# MOTOR.net
KiCad netlist of a schematic drawn in EAGLE
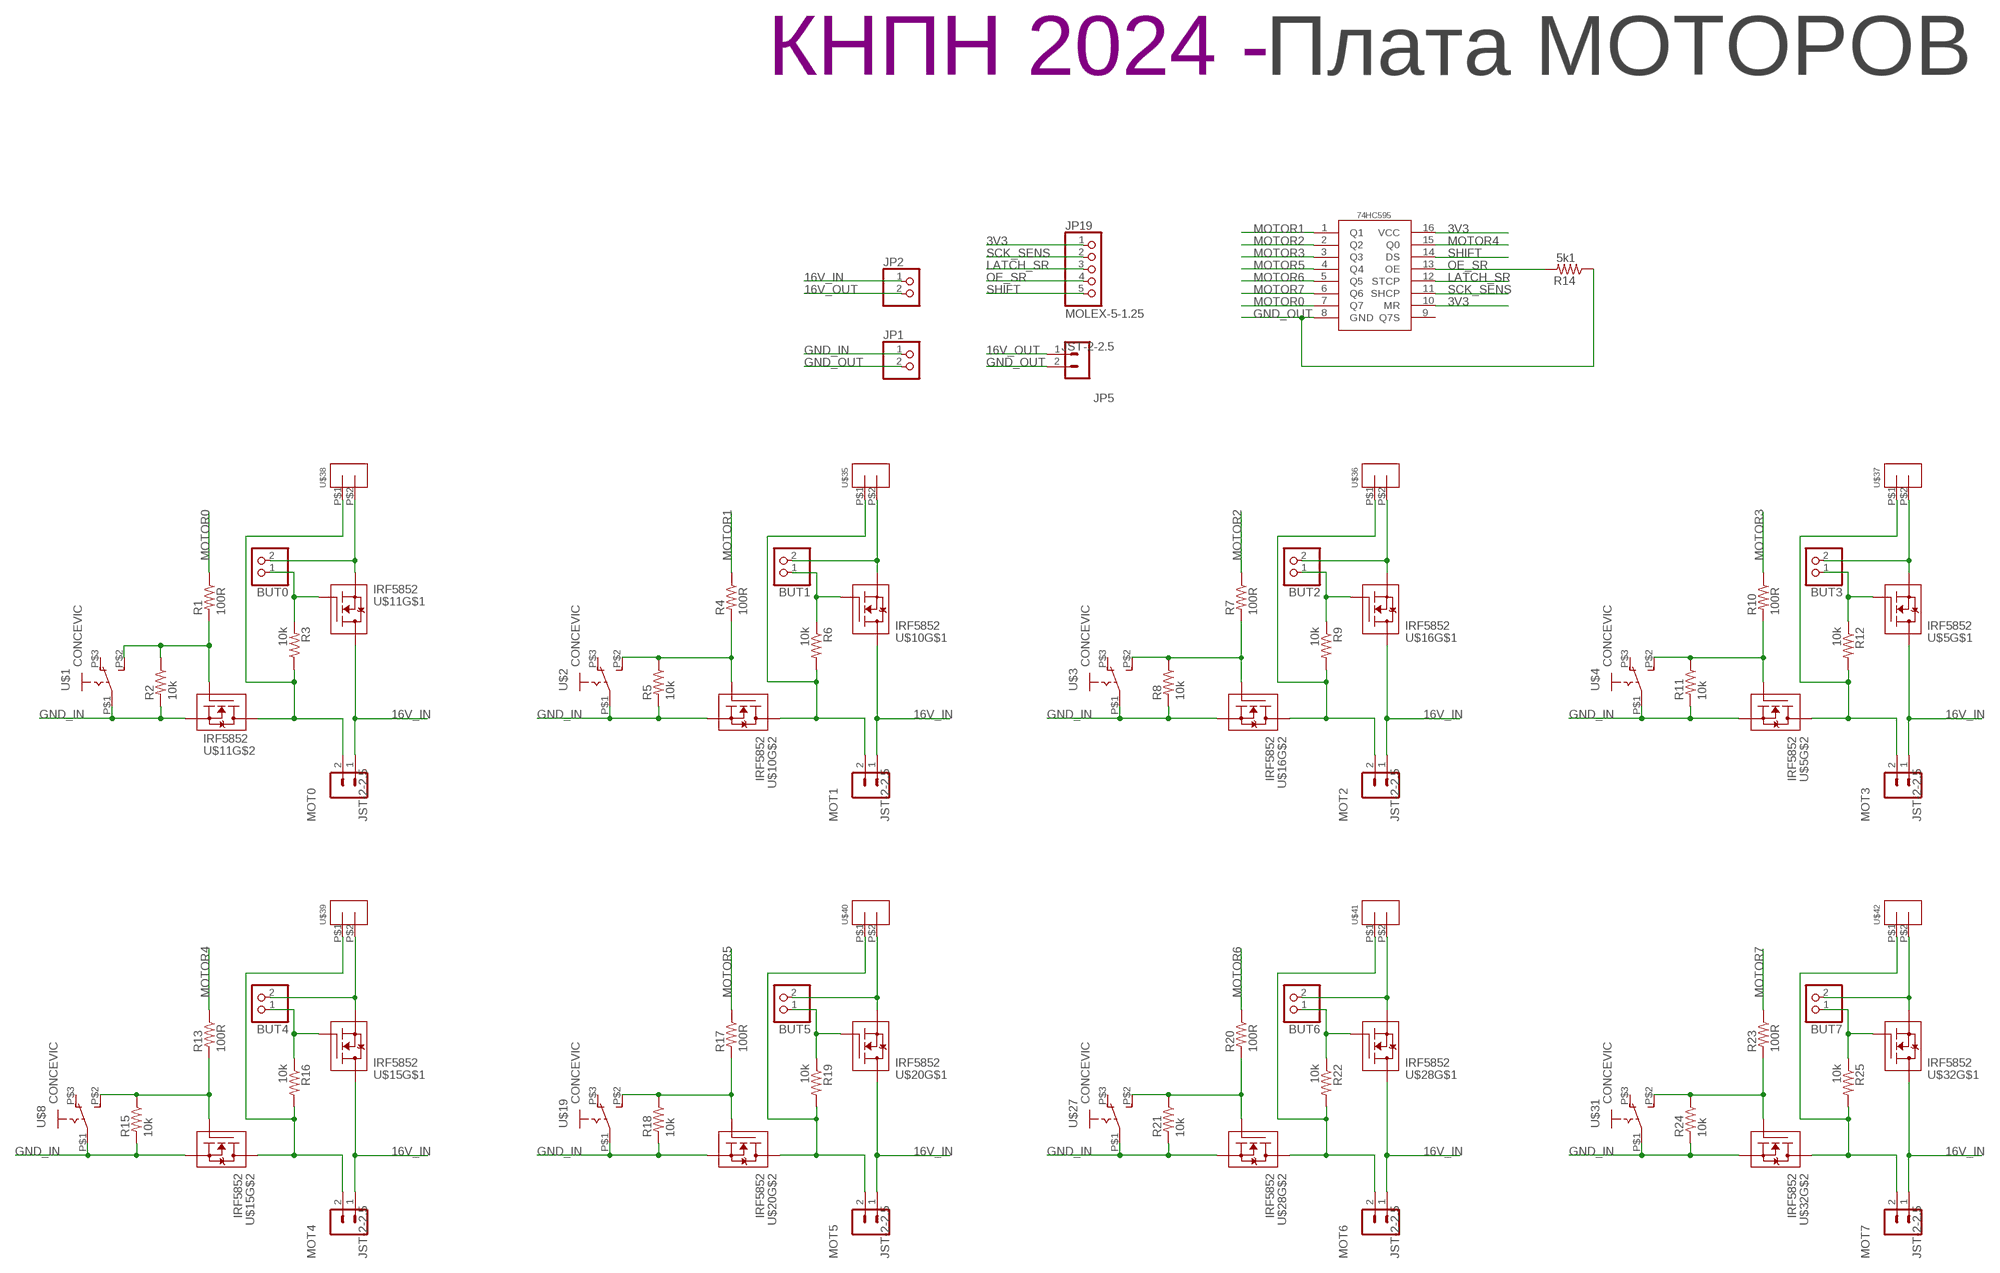
[diagram p0: schematic, sheet 1]

(export (version "E")
  (design (tool "Eeschema 10.0.6"))
  (components
    (comp (ref "BUT0")
      (value "PINHD-1X2")
      (footprint "eagle-import:1X02")
      (libsource (lib "eagle-import") (part "PINHD-1X2"))
    )
    (comp (ref "BUT1")
      (value "PINHD-1X2")
      (footprint "eagle-import:1X02")
      (libsource (lib "eagle-import") (part "PINHD-1X2"))
    )
    (comp (ref "BUT2")
      (value "PINHD-1X2")
      (footprint "eagle-import:1X02")
      (libsource (lib "eagle-import") (part "PINHD-1X2"))
    )
    (comp (ref "BUT3")
      (value "PINHD-1X2")
      (footprint "eagle-import:1X02")
      (libsource (lib "eagle-import") (part "PINHD-1X2"))
    )
    (comp (ref "BUT4")
      (value "PINHD-1X2")
      (footprint "eagle-import:1X02")
      (libsource (lib "eagle-import") (part "PINHD-1X2"))
    )
    (comp (ref "BUT5")
      (value "PINHD-1X2")
      (footprint "eagle-import:1X02")
      (libsource (lib "eagle-import") (part "PINHD-1X2"))
    )
    (comp (ref "BUT6")
      (value "PINHD-1X2")
      (footprint "eagle-import:1X02")
      (libsource (lib "eagle-import") (part "PINHD-1X2"))
    )
    (comp (ref "BUT7")
      (value "PINHD-1X2")
      (footprint "eagle-import:1X02")
      (libsource (lib "eagle-import") (part "PINHD-1X2"))
    )
    (comp (ref "JP1")
      (value "PINHD-1X2/90")
      (footprint "eagle-import:1X02_90")
      (libsource (lib "eagle-import") (part "PINHD-1X2/90"))
    )
    (comp (ref "JP2")
      (value "PINHD-1X2/90")
      (footprint "eagle-import:1X02_90")
      (libsource (lib "eagle-import") (part "PINHD-1X2/90"))
    )
    (comp (ref "JP5")
      (value "JST-2-2.5")
      (footprint "eagle-import:JST-2-2.5")
      (libsource (lib "eagle-import") (part "JST-2-2.5"))
    )
    (comp (ref "JP19")
      (value "MOLEX-5-1.25")
      (footprint "eagle-import:53047-05")
      (libsource (lib "eagle-import") (part "MOLEX-5-1.25"))
    )
    (comp (ref "MOT0")
      (value "JST-2-2.5")
      (footprint "eagle-import:JST-2-2.5")
      (libsource (lib "eagle-import") (part "JST-2-2.5"))
    )
    (comp (ref "MOT1")
      (value "JST-2-2.5")
      (footprint "eagle-import:JST-2-2.5")
      (libsource (lib "eagle-import") (part "JST-2-2.5"))
    )
    (comp (ref "MOT2")
      (value "JST-2-2.5")
      (footprint "eagle-import:JST-2-2.5")
      (libsource (lib "eagle-import") (part "JST-2-2.5"))
    )
    (comp (ref "MOT3")
      (value "JST-2-2.5")
      (footprint "eagle-import:JST-2-2.5")
      (libsource (lib "eagle-import") (part "JST-2-2.5"))
    )
    (comp (ref "MOT4")
      (value "JST-2-2.5")
      (footprint "eagle-import:JST-2-2.5")
      (libsource (lib "eagle-import") (part "JST-2-2.5"))
    )
    (comp (ref "MOT5")
      (value "JST-2-2.5")
      (footprint "eagle-import:JST-2-2.5")
      (libsource (lib "eagle-import") (part "JST-2-2.5"))
    )
    (comp (ref "MOT6")
      (value "JST-2-2.5")
      (footprint "eagle-import:JST-2-2.5")
      (libsource (lib "eagle-import") (part "JST-2-2.5"))
    )
    (comp (ref "MOT7")
      (value "JST-2-2.5")
      (footprint "eagle-import:JST-2-2.5")
      (libsource (lib "eagle-import") (part "JST-2-2.5"))
    )
    (comp (ref "R1")
      (value "100R")
      (footprint "eagle-import:R0603")
      (libsource (lib "eagle-import") (part "R-US_R0603"))
    )
    (comp (ref "R2")
      (value "10k")
      (footprint "eagle-import:R0603")
      (libsource (lib "eagle-import") (part "R-US_R0603"))
    )
    (comp (ref "R3")
      (value "10k")
      (footprint "eagle-import:R0603")
      (libsource (lib "eagle-import") (part "R-US_R0603"))
    )
    (comp (ref "R4")
      (value "100R")
      (footprint "eagle-import:R0603")
      (libsource (lib "eagle-import") (part "R-US_R0603"))
    )
    (comp (ref "R5")
      (value "10k")
      (footprint "eagle-import:R0603")
      (libsource (lib "eagle-import") (part "R-US_R0603"))
    )
    (comp (ref "R6")
      (value "10k")
      (footprint "eagle-import:R0603")
      (libsource (lib "eagle-import") (part "R-US_R0603"))
    )
    (comp (ref "R7")
      (value "100R")
      (footprint "eagle-import:R0603")
      (libsource (lib "eagle-import") (part "R-US_R0603"))
    )
    (comp (ref "R8")
      (value "10k")
      (footprint "eagle-import:R0603")
      (libsource (lib "eagle-import") (part "R-US_R0603"))
    )
    (comp (ref "R9")
      (value "10k")
      (footprint "eagle-import:R0603")
      (libsource (lib "eagle-import") (part "R-US_R0603"))
    )
    (comp (ref "R10")
      (value "100R")
      (footprint "eagle-import:R0603")
      (libsource (lib "eagle-import") (part "R-US_R0603"))
    )
    (comp (ref "R11")
      (value "10k")
      (footprint "eagle-import:R0603")
      (libsource (lib "eagle-import") (part "R-US_R0603"))
    )
    (comp (ref "R12")
      (value "10k")
      (footprint "eagle-import:R0603")
      (libsource (lib "eagle-import") (part "R-US_R0603"))
    )
    (comp (ref "R13")
      (value "100R")
      (footprint "eagle-import:R0603")
      (libsource (lib "eagle-import") (part "R-US_R0603"))
    )
    (comp (ref "R14")
      (value "5k1")
      (footprint "eagle-import:R0603")
      (libsource (lib "eagle-import") (part "R-US_R0603"))
    )
    (comp (ref "R15")
      (value "10k")
      (footprint "eagle-import:R0603")
      (libsource (lib "eagle-import") (part "R-US_R0603"))
    )
    (comp (ref "R16")
      (value "10k")
      (footprint "eagle-import:R0603")
      (libsource (lib "eagle-import") (part "R-US_R0603"))
    )
    (comp (ref "R17")
      (value "100R")
      (footprint "eagle-import:R0603")
      (libsource (lib "eagle-import") (part "R-US_R0603"))
    )
    (comp (ref "R18")
      (value "10k")
      (footprint "eagle-import:R0603")
      (libsource (lib "eagle-import") (part "R-US_R0603"))
    )
    (comp (ref "R19")
      (value "10k")
      (footprint "eagle-import:R0603")
      (libsource (lib "eagle-import") (part "R-US_R0603"))
    )
    (comp (ref "R20")
      (value "100R")
      (footprint "eagle-import:R0603")
      (libsource (lib "eagle-import") (part "R-US_R0603"))
    )
    (comp (ref "R21")
      (value "10k")
      (footprint "eagle-import:R0603")
      (libsource (lib "eagle-import") (part "R-US_R0603"))
    )
    (comp (ref "R22")
      (value "10k")
      (footprint "eagle-import:R0603")
      (libsource (lib "eagle-import") (part "R-US_R0603"))
    )
    (comp (ref "R23")
      (value "100R")
      (footprint "eagle-import:R0603")
      (libsource (lib "eagle-import") (part "R-US_R0603"))
    )
    (comp (ref "R24")
      (value "10k")
      (footprint "eagle-import:R0603")
      (libsource (lib "eagle-import") (part "R-US_R0603"))
    )
    (comp (ref "R25")
      (value "10k")
      (footprint "eagle-import:R0603")
      (libsource (lib "eagle-import") (part "R-US_R0603"))
    )
    (comp (ref "U$1")
      (value "CONCEVIC")
      (footprint "eagle-import:CONCEVIC")
      (libsource (lib "eagle-import") (part "CONCEVIC"))
    )
    (comp (ref "U$2")
      (value "CONCEVIC")
      (footprint "eagle-import:CONCEVIC")
      (libsource (lib "eagle-import") (part "CONCEVIC"))
    )
    (comp (ref "U$3")
      (value "CONCEVIC")
      (footprint "eagle-import:CONCEVIC")
      (libsource (lib "eagle-import") (part "CONCEVIC"))
    )
    (comp (ref "U$4")
      (value "CONCEVIC")
      (footprint "eagle-import:CONCEVIC")
      (libsource (lib "eagle-import") (part "CONCEVIC"))
    )
    (comp (ref "U$5")
      (value "IRF5852")
      (footprint "eagle-import:TSOP-6")
      (libsource (lib "eagle-import") (part "IRF5852"))
    )
    (comp (ref "U$8")
      (value "CONCEVIC")
      (footprint "eagle-import:CONCEVIC")
      (libsource (lib "eagle-import") (part "CONCEVIC"))
    )
    (comp (ref "U$9")
      (value "Плата МОТОРОВ")
      (footprint "eagle-import:LOGO")
      (libsource (lib "eagle-import") (part "LOGOPCB-{dblquote}{dblquote}"))
    )
    (comp (ref "U$10")
      (value "IRF5852")
      (footprint "eagle-import:TSOP-6")
      (libsource (lib "eagle-import") (part "IRF5852"))
    )
    (comp (ref "U$11")
      (value "IRF5852")
      (footprint "eagle-import:TSOP-6")
      (libsource (lib "eagle-import") (part "IRF5852"))
    )
    (comp (ref "U$13")
      (value "74HC595")
      (footprint "eagle-import:TSSOP16")
      (libsource (lib "eagle-import") (part "74HC595"))
    )
    (comp (ref "U$15")
      (value "IRF5852")
      (footprint "eagle-import:TSOP-6")
      (libsource (lib "eagle-import") (part "IRF5852"))
    )
    (comp (ref "U$16")
      (value "IRF5852")
      (footprint "eagle-import:TSOP-6")
      (libsource (lib "eagle-import") (part "IRF5852"))
    )
    (comp (ref "U$19")
      (value "CONCEVIC")
      (footprint "eagle-import:CONCEVIC")
      (libsource (lib "eagle-import") (part "CONCEVIC"))
    )
    (comp (ref "U$20")
      (value "IRF5852")
      (footprint "eagle-import:TSOP-6")
      (libsource (lib "eagle-import") (part "IRF5852"))
    )
    (comp (ref "U$27")
      (value "CONCEVIC")
      (footprint "eagle-import:CONCEVIC")
      (libsource (lib "eagle-import") (part "CONCEVIC"))
    )
    (comp (ref "U$28")
      (value "IRF5852")
      (footprint "eagle-import:TSOP-6")
      (libsource (lib "eagle-import") (part "IRF5852"))
    )
    (comp (ref "U$31")
      (value "CONCEVIC")
      (footprint "eagle-import:CONCEVIC")
      (libsource (lib "eagle-import") (part "CONCEVIC"))
    )
    (comp (ref "U$32")
      (value "IRF5852")
      (footprint "eagle-import:TSOP-6")
      (libsource (lib "eagle-import") (part "IRF5852"))
    )
    (comp (ref "U$35")
      (value "CONTACT_SIDE_4MM_2PIN")
      (footprint "eagle-import:CONTACT_SIDE_4MM_2PIN")
      (libsource (lib "eagle-import") (part "CONTACT_SIDE_4MM_2PIN"))
    )
    (comp (ref "U$36")
      (value "CONTACT_SIDE_4MM_2PIN")
      (footprint "eagle-import:CONTACT_SIDE_4MM_2PIN")
      (libsource (lib "eagle-import") (part "CONTACT_SIDE_4MM_2PIN"))
    )
    (comp (ref "U$37")
      (value "CONTACT_SIDE_4MM_2PIN")
      (footprint "eagle-import:CONTACT_SIDE_4MM_2PIN")
      (libsource (lib "eagle-import") (part "CONTACT_SIDE_4MM_2PIN"))
    )
    (comp (ref "U$38")
      (value "CONTACT_SIDE_4MM_2PIN")
      (footprint "eagle-import:CONTACT_SIDE_4MM_2PIN")
      (libsource (lib "eagle-import") (part "CONTACT_SIDE_4MM_2PIN"))
    )
    (comp (ref "U$39")
      (value "CONTACT_SIDE_4MM_2PIN")
      (footprint "eagle-import:CONTACT_SIDE_4MM_2PIN")
      (libsource (lib "eagle-import") (part "CONTACT_SIDE_4MM_2PIN"))
    )
    (comp (ref "U$40")
      (value "CONTACT_SIDE_4MM_2PIN")
      (footprint "eagle-import:CONTACT_SIDE_4MM_2PIN")
      (libsource (lib "eagle-import") (part "CONTACT_SIDE_4MM_2PIN"))
    )
    (comp (ref "U$41")
      (value "CONTACT_SIDE_4MM_2PIN")
      (footprint "eagle-import:CONTACT_SIDE_4MM_2PIN")
      (libsource (lib "eagle-import") (part "CONTACT_SIDE_4MM_2PIN"))
    )
    (comp (ref "U$42")
      (value "CONTACT_SIDE_4MM_2PIN")
      (footprint "eagle-import:CONTACT_SIDE_4MM_2PIN")
      (libsource (lib "eagle-import") (part "CONTACT_SIDE_4MM_2PIN"))
    )
  )
  (nets
    (net (code "1") (name "/3V3") (class "Default")
      (node (ref "JP19") (pin "1") (pinfunction "1_1") (pintype "passive"))
      (node (ref "U$13") (pin "10") (pinfunction "MR_10") (pintype "bidirectional"))
      (node (ref "U$13") (pin "16") (pinfunction "VCC_16") (pintype "bidirectional"))
    )
    (net (code "2") (name "/16V_IN") (class "Default")
      (node (ref "JP2") (pin "1") (pinfunction "1_1") (pintype "passive"))
      (node (ref "MOT0") (pin "1") (pinfunction "1_1") (pintype "passive"))
      (node (ref "MOT1") (pin "1") (pinfunction "1_1") (pintype "passive"))
      (node (ref "MOT2") (pin "1") (pinfunction "1_1") (pintype "passive"))
      (node (ref "MOT3") (pin "1") (pinfunction "1_1") (pintype "passive"))
      (node (ref "MOT4") (pin "1") (pinfunction "1_1") (pintype "passive"))
      (node (ref "MOT5") (pin "1") (pinfunction "1_1") (pintype "passive"))
      (node (ref "MOT6") (pin "1") (pinfunction "1_1") (pintype "passive"))
      (node (ref "MOT7") (pin "1") (pinfunction "1_1") (pintype "passive"))
      (node (ref "U$10") (pin "P$6") (pinfunction "D1_P$6") (pintype "passive"))
      (node (ref "U$11") (pin "P$6") (pinfunction "D1_P$6") (pintype "passive"))
      (node (ref "U$15") (pin "P$6") (pinfunction "D1_P$6") (pintype "passive"))
      (node (ref "U$16") (pin "P$6") (pinfunction "D1_P$6") (pintype "passive"))
      (node (ref "U$20") (pin "P$6") (pinfunction "D1_P$6") (pintype "passive"))
      (node (ref "U$28") (pin "P$6") (pinfunction "D1_P$6") (pintype "passive"))
      (node (ref "U$32") (pin "P$6") (pinfunction "D1_P$6") (pintype "passive"))
      (node (ref "U$5") (pin "P$6") (pinfunction "D1_P$6") (pintype "passive"))
    )
    (net (code "3") (name "/16V_OUT") (class "Default")
      (node (ref "JP2") (pin "2") (pinfunction "2_2") (pintype "passive"))
      (node (ref "JP5") (pin "1") (pinfunction "1_1") (pintype "passive"))
    )
    (net (code "4") (name "/GND_IN") (class "Default")
      (node (ref "JP1") (pin "1") (pinfunction "1_1") (pintype "passive"))
      (node (ref "R11") (pin "2") (pinfunction "2_2") (pintype "passive"))
      (node (ref "R15") (pin "2") (pinfunction "2_2") (pintype "passive"))
      (node (ref "R18") (pin "2") (pinfunction "2_2") (pintype "passive"))
      (node (ref "R2") (pin "2") (pinfunction "2_2") (pintype "passive"))
      (node (ref "R21") (pin "2") (pinfunction "2_2") (pintype "passive"))
      (node (ref "R24") (pin "2") (pinfunction "2_2") (pintype "passive"))
      (node (ref "R5") (pin "2") (pinfunction "2_2") (pintype "passive"))
      (node (ref "R8") (pin "2") (pinfunction "2_2") (pintype "passive"))
      (node (ref "U$1") (pin "P$1") (pinfunction "P_P$1") (pintype "passive"))
      (node (ref "U$10") (pin "P$2") (pinfunction "S1_P$2") (pintype "passive"))
      (node (ref "U$11") (pin "P$2") (pinfunction "S1_P$2") (pintype "passive"))
      (node (ref "U$15") (pin "P$2") (pinfunction "S1_P$2") (pintype "passive"))
      (node (ref "U$16") (pin "P$2") (pinfunction "S1_P$2") (pintype "passive"))
      (node (ref "U$19") (pin "P$1") (pinfunction "P_P$1") (pintype "passive"))
      (node (ref "U$2") (pin "P$1") (pinfunction "P_P$1") (pintype "passive"))
      (node (ref "U$20") (pin "P$2") (pinfunction "S1_P$2") (pintype "passive"))
      (node (ref "U$27") (pin "P$1") (pinfunction "P_P$1") (pintype "passive"))
      (node (ref "U$28") (pin "P$2") (pinfunction "S1_P$2") (pintype "passive"))
      (node (ref "U$3") (pin "P$1") (pinfunction "P_P$1") (pintype "passive"))
      (node (ref "U$31") (pin "P$1") (pinfunction "P_P$1") (pintype "passive"))
      (node (ref "U$32") (pin "P$2") (pinfunction "S1_P$2") (pintype "passive"))
      (node (ref "U$4") (pin "P$1") (pinfunction "P_P$1") (pintype "passive"))
      (node (ref "U$5") (pin "P$2") (pinfunction "S1_P$2") (pintype "passive"))
      (node (ref "U$8") (pin "P$1") (pinfunction "P_P$1") (pintype "passive"))
    )
    (net (code "5") (name "/GND_OUT") (class "Default")
      (node (ref "JP1") (pin "2") (pinfunction "2_2") (pintype "passive"))
      (node (ref "JP5") (pin "2") (pinfunction "2_2") (pintype "passive"))
      (node (ref "R14") (pin "1") (pinfunction "1_1") (pintype "passive"))
      (node (ref "U$13") (pin "8") (pinfunction "GND_8") (pintype "bidirectional"))
    )
    (net (code "6") (name "/LATCH_SR") (class "Default")
      (node (ref "JP19") (pin "3") (pinfunction "3_3") (pintype "passive"))
      (node (ref "U$13") (pin "12") (pinfunction "STCP_12") (pintype "bidirectional"))
    )
    (net (code "7") (name "/MOTOR0") (class "Default")
      (node (ref "R1") (pin "1") (pinfunction "1_1") (pintype "passive"))
      (node (ref "U$13") (pin "7") (pinfunction "Q7_7") (pintype "bidirectional"))
    )
    (net (code "8") (name "/MOTOR1") (class "Default")
      (node (ref "R4") (pin "1") (pinfunction "1_1") (pintype "passive"))
      (node (ref "U$13") (pin "1") (pinfunction "Q1_1") (pintype "bidirectional"))
    )
    (net (code "9") (name "/MOTOR2") (class "Default")
      (node (ref "R7") (pin "1") (pinfunction "1_1") (pintype "passive"))
      (node (ref "U$13") (pin "2") (pinfunction "Q2_2") (pintype "bidirectional"))
    )
    (net (code "10") (name "/MOTOR3") (class "Default")
      (node (ref "R10") (pin "1") (pinfunction "1_1") (pintype "passive"))
      (node (ref "U$13") (pin "3") (pinfunction "Q3_3") (pintype "bidirectional"))
    )
    (net (code "11") (name "/MOTOR4") (class "Default")
      (node (ref "R13") (pin "1") (pinfunction "1_1") (pintype "passive"))
      (node (ref "U$13") (pin "15") (pinfunction "Q0_15") (pintype "bidirectional"))
    )
    (net (code "12") (name "/MOTOR5") (class "Default")
      (node (ref "R17") (pin "1") (pinfunction "1_1") (pintype "passive"))
      (node (ref "U$13") (pin "4") (pinfunction "Q4_4") (pintype "bidirectional"))
    )
    (net (code "13") (name "/MOTOR6") (class "Default")
      (node (ref "R20") (pin "1") (pinfunction "1_1") (pintype "passive"))
      (node (ref "U$13") (pin "5") (pinfunction "Q5_5") (pintype "bidirectional"))
    )
    (net (code "14") (name "/MOTOR7") (class "Default")
      (node (ref "R23") (pin "1") (pinfunction "1_1") (pintype "passive"))
      (node (ref "U$13") (pin "6") (pinfunction "Q6_6") (pintype "bidirectional"))
    )
    (net (code "15") (name "/OE_SR") (class "Default")
      (node (ref "JP19") (pin "4") (pinfunction "4_4") (pintype "passive"))
      (node (ref "R14") (pin "2") (pinfunction "2_2") (pintype "passive"))
      (node (ref "U$13") (pin "13") (pinfunction "OE_13") (pintype "bidirectional"))
    )
    (net (code "16") (name "/SCK_SENS") (class "Default")
      (node (ref "JP19") (pin "2") (pinfunction "2_2") (pintype "passive"))
      (node (ref "U$13") (pin "11") (pinfunction "SHCP_11") (pintype "bidirectional"))
    )
    (net (code "17") (name "/SHIFT") (class "Default")
      (node (ref "JP19") (pin "5") (pinfunction "5_5") (pintype "passive"))
      (node (ref "U$13") (pin "14") (pinfunction "DS_14") (pintype "bidirectional"))
    )
    (net (code "18") (name "Net-(U$1-S)") (class "Default")
      (node (ref "R1") (pin "2") (pinfunction "2_2") (pintype "passive"))
      (node (ref "R2") (pin "1") (pinfunction "1_1") (pintype "passive"))
      (node (ref "U$1") (pin "P$2") (pinfunction "S_P$2") (pintype "passive"))
      (node (ref "U$11") (pin "P$3") (pinfunction "G1_P$3") (pintype "passive"))
    )
    (net (code "19") (name "Net-(U$4-S)") (class "Default")
      (node (ref "R10") (pin "2") (pinfunction "2_2") (pintype "passive"))
      (node (ref "R11") (pin "1") (pinfunction "1_1") (pintype "passive"))
      (node (ref "U$4") (pin "P$2") (pinfunction "S_P$2") (pintype "passive"))
      (node (ref "U$5") (pin "P$3") (pinfunction "G1_P$3") (pintype "passive"))
    )
    (net (code "20") (name "Net-(U$5A-G1)") (class "Default")
      (node (ref "BUT3") (pin "1") (pinfunction "1_1") (pintype "passive"))
      (node (ref "R12") (pin "1") (pinfunction "1_1") (pintype "passive"))
      (node (ref "U$5") (pin "P$1") (pinfunction "G1_P$1") (pintype "passive"))
    )
    (net (code "21") (name "Net-(U$5A-S1)") (class "Default")
      (node (ref "BUT3") (pin "2") (pinfunction "2_2") (pintype "passive"))
      (node (ref "U$37") (pin "P$2") (pinfunction "P$2_P$2") (pintype "bidirectional"))
      (node (ref "U$5") (pin "P$5") (pinfunction "S1_P$5") (pintype "passive"))
    )
    (net (code "22") (name "Net-(U$5B-D1)") (class "Default")
      (node (ref "MOT3") (pin "2") (pinfunction "2_2") (pintype "passive"))
      (node (ref "R12") (pin "2") (pinfunction "2_2") (pintype "passive"))
      (node (ref "U$37") (pin "P$1") (pinfunction "P$1_P$1") (pintype "bidirectional"))
      (node (ref "U$5") (pin "P$4") (pinfunction "D1_P$4") (pintype "passive"))
    )
    (net (code "23") (name "Net-(U$10A-G1)") (class "Default")
      (node (ref "BUT1") (pin "1") (pinfunction "1_1") (pintype "passive"))
      (node (ref "R6") (pin "1") (pinfunction "1_1") (pintype "passive"))
      (node (ref "U$10") (pin "P$1") (pinfunction "G1_P$1") (pintype "passive"))
    )
    (net (code "24") (name "Net-(U$10A-S1)") (class "Default")
      (node (ref "BUT1") (pin "2") (pinfunction "2_2") (pintype "passive"))
      (node (ref "U$10") (pin "P$5") (pinfunction "S1_P$5") (pintype "passive"))
      (node (ref "U$35") (pin "P$2") (pinfunction "P$2_P$2") (pintype "bidirectional"))
    )
    (net (code "25") (name "Net-(U$10B-D1)") (class "Default")
      (node (ref "MOT1") (pin "2") (pinfunction "2_2") (pintype "passive"))
      (node (ref "R6") (pin "2") (pinfunction "2_2") (pintype "passive"))
      (node (ref "U$10") (pin "P$4") (pinfunction "D1_P$4") (pintype "passive"))
      (node (ref "U$35") (pin "P$1") (pinfunction "P$1_P$1") (pintype "bidirectional"))
    )
    (net (code "26") (name "Net-(U$10B-G1)") (class "Default")
      (node (ref "R4") (pin "2") (pinfunction "2_2") (pintype "passive"))
      (node (ref "R5") (pin "1") (pinfunction "1_1") (pintype "passive"))
      (node (ref "U$10") (pin "P$3") (pinfunction "G1_P$3") (pintype "passive"))
      (node (ref "U$2") (pin "P$2") (pinfunction "S_P$2") (pintype "passive"))
    )
    (net (code "27") (name "Net-(U$11A-G1)") (class "Default")
      (node (ref "BUT0") (pin "1") (pinfunction "1_1") (pintype "passive"))
      (node (ref "R3") (pin "2") (pinfunction "2_2") (pintype "passive"))
      (node (ref "U$11") (pin "P$1") (pinfunction "G1_P$1") (pintype "passive"))
    )
    (net (code "28") (name "Net-(U$11A-S1)") (class "Default")
      (node (ref "BUT0") (pin "2") (pinfunction "2_2") (pintype "passive"))
      (node (ref "U$11") (pin "P$5") (pinfunction "S1_P$5") (pintype "passive"))
      (node (ref "U$38") (pin "P$2") (pinfunction "P$2_P$2") (pintype "bidirectional"))
    )
    (net (code "29") (name "Net-(U$11B-D1)") (class "Default")
      (node (ref "MOT0") (pin "2") (pinfunction "2_2") (pintype "passive"))
      (node (ref "R3") (pin "1") (pinfunction "1_1") (pintype "passive"))
      (node (ref "U$11") (pin "P$4") (pinfunction "D1_P$4") (pintype "passive"))
      (node (ref "U$38") (pin "P$1") (pinfunction "P$1_P$1") (pintype "bidirectional"))
    )
    (net (code "30") (name "Net-(U$15A-G1)") (class "Default")
      (node (ref "BUT4") (pin "1") (pinfunction "1_1") (pintype "passive"))
      (node (ref "R16") (pin "1") (pinfunction "1_1") (pintype "passive"))
      (node (ref "U$15") (pin "P$1") (pinfunction "G1_P$1") (pintype "passive"))
    )
    (net (code "31") (name "Net-(U$15A-S1)") (class "Default")
      (node (ref "BUT4") (pin "2") (pinfunction "2_2") (pintype "passive"))
      (node (ref "U$15") (pin "P$5") (pinfunction "S1_P$5") (pintype "passive"))
      (node (ref "U$39") (pin "P$2") (pinfunction "P$2_P$2") (pintype "bidirectional"))
    )
    (net (code "32") (name "Net-(U$15B-D1)") (class "Default")
      (node (ref "MOT4") (pin "2") (pinfunction "2_2") (pintype "passive"))
      (node (ref "R16") (pin "2") (pinfunction "2_2") (pintype "passive"))
      (node (ref "U$15") (pin "P$4") (pinfunction "D1_P$4") (pintype "passive"))
      (node (ref "U$39") (pin "P$1") (pinfunction "P$1_P$1") (pintype "bidirectional"))
    )
    (net (code "33") (name "Net-(U$15B-G1)") (class "Default")
      (node (ref "R13") (pin "2") (pinfunction "2_2") (pintype "passive"))
      (node (ref "R15") (pin "1") (pinfunction "1_1") (pintype "passive"))
      (node (ref "U$15") (pin "P$3") (pinfunction "G1_P$3") (pintype "passive"))
      (node (ref "U$8") (pin "P$2") (pinfunction "S_P$2") (pintype "passive"))
    )
    (net (code "34") (name "Net-(U$16A-G1)") (class "Default")
      (node (ref "BUT2") (pin "1") (pinfunction "1_1") (pintype "passive"))
      (node (ref "R9") (pin "1") (pinfunction "1_1") (pintype "passive"))
      (node (ref "U$16") (pin "P$1") (pinfunction "G1_P$1") (pintype "passive"))
    )
    (net (code "35") (name "Net-(U$16A-S1)") (class "Default")
      (node (ref "BUT2") (pin "2") (pinfunction "2_2") (pintype "passive"))
      (node (ref "U$16") (pin "P$5") (pinfunction "S1_P$5") (pintype "passive"))
      (node (ref "U$36") (pin "P$2") (pinfunction "P$2_P$2") (pintype "bidirectional"))
    )
    (net (code "36") (name "Net-(U$16B-D1)") (class "Default")
      (node (ref "MOT2") (pin "2") (pinfunction "2_2") (pintype "passive"))
      (node (ref "R9") (pin "2") (pinfunction "2_2") (pintype "passive"))
      (node (ref "U$16") (pin "P$4") (pinfunction "D1_P$4") (pintype "passive"))
      (node (ref "U$36") (pin "P$1") (pinfunction "P$1_P$1") (pintype "bidirectional"))
    )
    (net (code "37") (name "Net-(U$16B-G1)") (class "Default")
      (node (ref "R7") (pin "2") (pinfunction "2_2") (pintype "passive"))
      (node (ref "R8") (pin "1") (pinfunction "1_1") (pintype "passive"))
      (node (ref "U$16") (pin "P$3") (pinfunction "G1_P$3") (pintype "passive"))
      (node (ref "U$3") (pin "P$2") (pinfunction "S_P$2") (pintype "passive"))
    )
    (net (code "38") (name "Net-(U$19-S)") (class "Default")
      (node (ref "R17") (pin "2") (pinfunction "2_2") (pintype "passive"))
      (node (ref "R18") (pin "1") (pinfunction "1_1") (pintype "passive"))
      (node (ref "U$19") (pin "P$2") (pinfunction "S_P$2") (pintype "passive"))
      (node (ref "U$20") (pin "P$3") (pinfunction "G1_P$3") (pintype "passive"))
    )
    (net (code "39") (name "Net-(U$20A-G1)") (class "Default")
      (node (ref "BUT5") (pin "1") (pinfunction "1_1") (pintype "passive"))
      (node (ref "R19") (pin "1") (pinfunction "1_1") (pintype "passive"))
      (node (ref "U$20") (pin "P$1") (pinfunction "G1_P$1") (pintype "passive"))
    )
    (net (code "40") (name "Net-(U$20A-S1)") (class "Default")
      (node (ref "BUT5") (pin "2") (pinfunction "2_2") (pintype "passive"))
      (node (ref "U$20") (pin "P$5") (pinfunction "S1_P$5") (pintype "passive"))
      (node (ref "U$40") (pin "P$2") (pinfunction "P$2_P$2") (pintype "bidirectional"))
    )
    (net (code "41") (name "Net-(U$20B-D1)") (class "Default")
      (node (ref "MOT5") (pin "2") (pinfunction "2_2") (pintype "passive"))
      (node (ref "R19") (pin "2") (pinfunction "2_2") (pintype "passive"))
      (node (ref "U$20") (pin "P$4") (pinfunction "D1_P$4") (pintype "passive"))
      (node (ref "U$40") (pin "P$1") (pinfunction "P$1_P$1") (pintype "bidirectional"))
    )
    (net (code "42") (name "Net-(U$27-S)") (class "Default")
      (node (ref "R20") (pin "2") (pinfunction "2_2") (pintype "passive"))
      (node (ref "R21") (pin "1") (pinfunction "1_1") (pintype "passive"))
      (node (ref "U$27") (pin "P$2") (pinfunction "S_P$2") (pintype "passive"))
      (node (ref "U$28") (pin "P$3") (pinfunction "G1_P$3") (pintype "passive"))
    )
    (net (code "43") (name "Net-(U$28A-G1)") (class "Default")
      (node (ref "BUT6") (pin "1") (pinfunction "1_1") (pintype "passive"))
      (node (ref "R22") (pin "1") (pinfunction "1_1") (pintype "passive"))
      (node (ref "U$28") (pin "P$1") (pinfunction "G1_P$1") (pintype "passive"))
    )
    (net (code "44") (name "Net-(U$28A-S1)") (class "Default")
      (node (ref "BUT6") (pin "2") (pinfunction "2_2") (pintype "passive"))
      (node (ref "U$28") (pin "P$5") (pinfunction "S1_P$5") (pintype "passive"))
      (node (ref "U$41") (pin "P$2") (pinfunction "P$2_P$2") (pintype "bidirectional"))
    )
    (net (code "45") (name "Net-(U$28B-D1)") (class "Default")
      (node (ref "MOT6") (pin "2") (pinfunction "2_2") (pintype "passive"))
      (node (ref "R22") (pin "2") (pinfunction "2_2") (pintype "passive"))
      (node (ref "U$28") (pin "P$4") (pinfunction "D1_P$4") (pintype "passive"))
      (node (ref "U$41") (pin "P$1") (pinfunction "P$1_P$1") (pintype "bidirectional"))
    )
    (net (code "46") (name "Net-(U$31-S)") (class "Default")
      (node (ref "R23") (pin "2") (pinfunction "2_2") (pintype "passive"))
      (node (ref "R24") (pin "1") (pinfunction "1_1") (pintype "passive"))
      (node (ref "U$31") (pin "P$2") (pinfunction "S_P$2") (pintype "passive"))
      (node (ref "U$32") (pin "P$3") (pinfunction "G1_P$3") (pintype "passive"))
    )
    (net (code "47") (name "Net-(U$32A-G1)") (class "Default")
      (node (ref "BUT7") (pin "1") (pinfunction "1_1") (pintype "passive"))
      (node (ref "R25") (pin "1") (pinfunction "1_1") (pintype "passive"))
      (node (ref "U$32") (pin "P$1") (pinfunction "G1_P$1") (pintype "passive"))
    )
    (net (code "48") (name "Net-(U$32A-S1)") (class "Default")
      (node (ref "BUT7") (pin "2") (pinfunction "2_2") (pintype "passive"))
      (node (ref "U$32") (pin "P$5") (pinfunction "S1_P$5") (pintype "passive"))
      (node (ref "U$42") (pin "P$2") (pinfunction "P$2_P$2") (pintype "bidirectional"))
    )
    (net (code "49") (name "Net-(U$32B-D1)") (class "Default")
      (node (ref "MOT7") (pin "2") (pinfunction "2_2") (pintype "passive"))
      (node (ref "R25") (pin "2") (pinfunction "2_2") (pintype "passive"))
      (node (ref "U$32") (pin "P$4") (pinfunction "D1_P$4") (pintype "passive"))
      (node (ref "U$42") (pin "P$1") (pinfunction "P$1_P$1") (pintype "bidirectional"))
    )
    (net (code "50") (name "unconnected-(U$1-O-PadP$3)") (class "Default")
      (node (ref "U$1") (pin "P$3") (pinfunction "O_P$3") (pintype "passive"))
    )
    (net (code "51") (name "unconnected-(U$2-O-PadP$3)") (class "Default")
      (node (ref "U$2") (pin "P$3") (pinfunction "O_P$3") (pintype "passive"))
    )
    (net (code "52") (name "unconnected-(U$3-O-PadP$3)") (class "Default")
      (node (ref "U$3") (pin "P$3") (pinfunction "O_P$3") (pintype "passive"))
    )
    (net (code "53") (name "unconnected-(U$4-O-PadP$3)") (class "Default")
      (node (ref "U$4") (pin "P$3") (pinfunction "O_P$3") (pintype "passive"))
    )
    (net (code "54") (name "unconnected-(U$8-O-PadP$3)") (class "Default")
      (node (ref "U$8") (pin "P$3") (pinfunction "O_P$3") (pintype "passive"))
    )
    (net (code "55") (name "unconnected-(U$13-Q7S-Pad9)") (class "Default")
      (node (ref "U$13") (pin "9") (pinfunction "Q7S_9") (pintype "bidirectional"))
    )
    (net (code "56") (name "unconnected-(U$19-O-PadP$3)") (class "Default")
      (node (ref "U$19") (pin "P$3") (pinfunction "O_P$3") (pintype "passive"))
    )
    (net (code "57") (name "unconnected-(U$27-O-PadP$3)") (class "Default")
      (node (ref "U$27") (pin "P$3") (pinfunction "O_P$3") (pintype "passive"))
    )
    (net (code "58") (name "unconnected-(U$31-O-PadP$3)") (class "Default")
      (node (ref "U$31") (pin "P$3") (pinfunction "O_P$3") (pintype "passive"))
    )
  )
)
